# Transistor_Circuit.net
KiCad netlist of a schematic drawn in Altium Designer
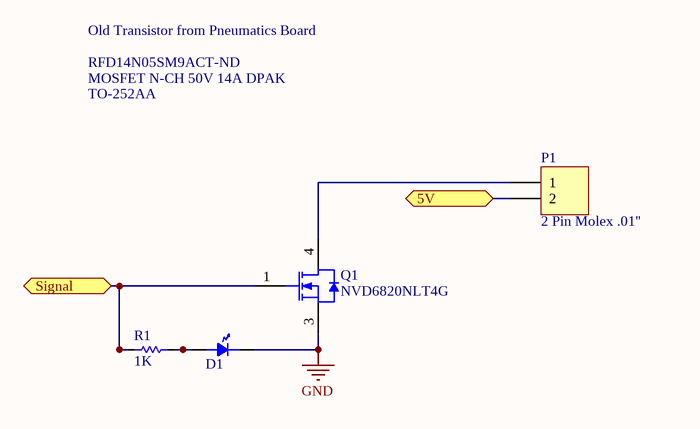
[diagram p0: Transistor Circuit.SchDoc]

(export (version "E")
  (design (tool "Eeschema 10.0.6"))
  (components
    (comp (ref "D1") (value "LED") (footprint "LED0805") (libsource (lib "URC_Lib") (part "LED")))
    (comp (ref "P1")
      (value "2 Pin Molex .01''")
      (footprint "HDR1X2")
      (description "Header, 2-Pin")
      (fields (field (name "PUBLISHER") "Altium Limited"))
      (libsource (lib "Miscellaneous Connectors") (part "Header 2"))
    )
    (comp (ref "Q1")
      (value "NVD6820NLT4G")
      (footprint "ONSC-DPAK-3-369C-01_V")
      (description "Power MOSFET, 90 V, 50 A, 17 mOhm, Single N-Channel, 3-Pin DPAK, Pb-Free, Tape and Reel")
      (fields (field (name "MANUFACTURER") "On Semiconductor"))
      (libsource (lib "ON Semi MOSFETs") (part "NVD6820NLT4G"))
    )
    (comp (ref "R1")
      (value "1K")
      (footprint "R0805")
      (description "Resistor")
      (fields (field (name "TOLERANCE") "5%"))
      (libsource (lib "component library URC") (part "Res"))
    )
  )
  (nets
    (net (code "1") (name "/5V") (class "Default")
      (node (ref "P1") (pin "2") (pinfunction "2_2") (pintype "passive"))
    )
    (net (code "2") (name "/Signal") (class "Default")
      (node (ref "Q1") (pin "1") (pinfunction "G_1") (pintype "passive"))
      (node (ref "R1") (pin "1") (pinfunction "1_1") (pintype "passive"))
    )
    (net (code "3") (name "GND") (class "Default")
      (node (ref "D1") (pin "1") (pinfunction "1_1") (pintype "passive"))
      (node (ref "Q1") (pin "3") (pinfunction "S_3") (pintype "passive"))
    )
    (net (code "4") (name "Net-(D1-Pad2)") (class "Default")
      (node (ref "D1") (pin "2") (pinfunction "2_2") (pintype "passive"))
      (node (ref "R1") (pin "2") (pinfunction "2_2") (pintype "passive"))
    )
    (net (code "5") (name "Net-(Q1-D)") (class "Default")
      (node (ref "P1") (pin "1") (pinfunction "1_1") (pintype "passive"))
      (node (ref "Q1") (pin "4") (pinfunction "D_4") (pintype "passive"))
    )
  )
)
